# 4_Sensing.net
KiCad netlist of a schematic drawn in Altium Designer
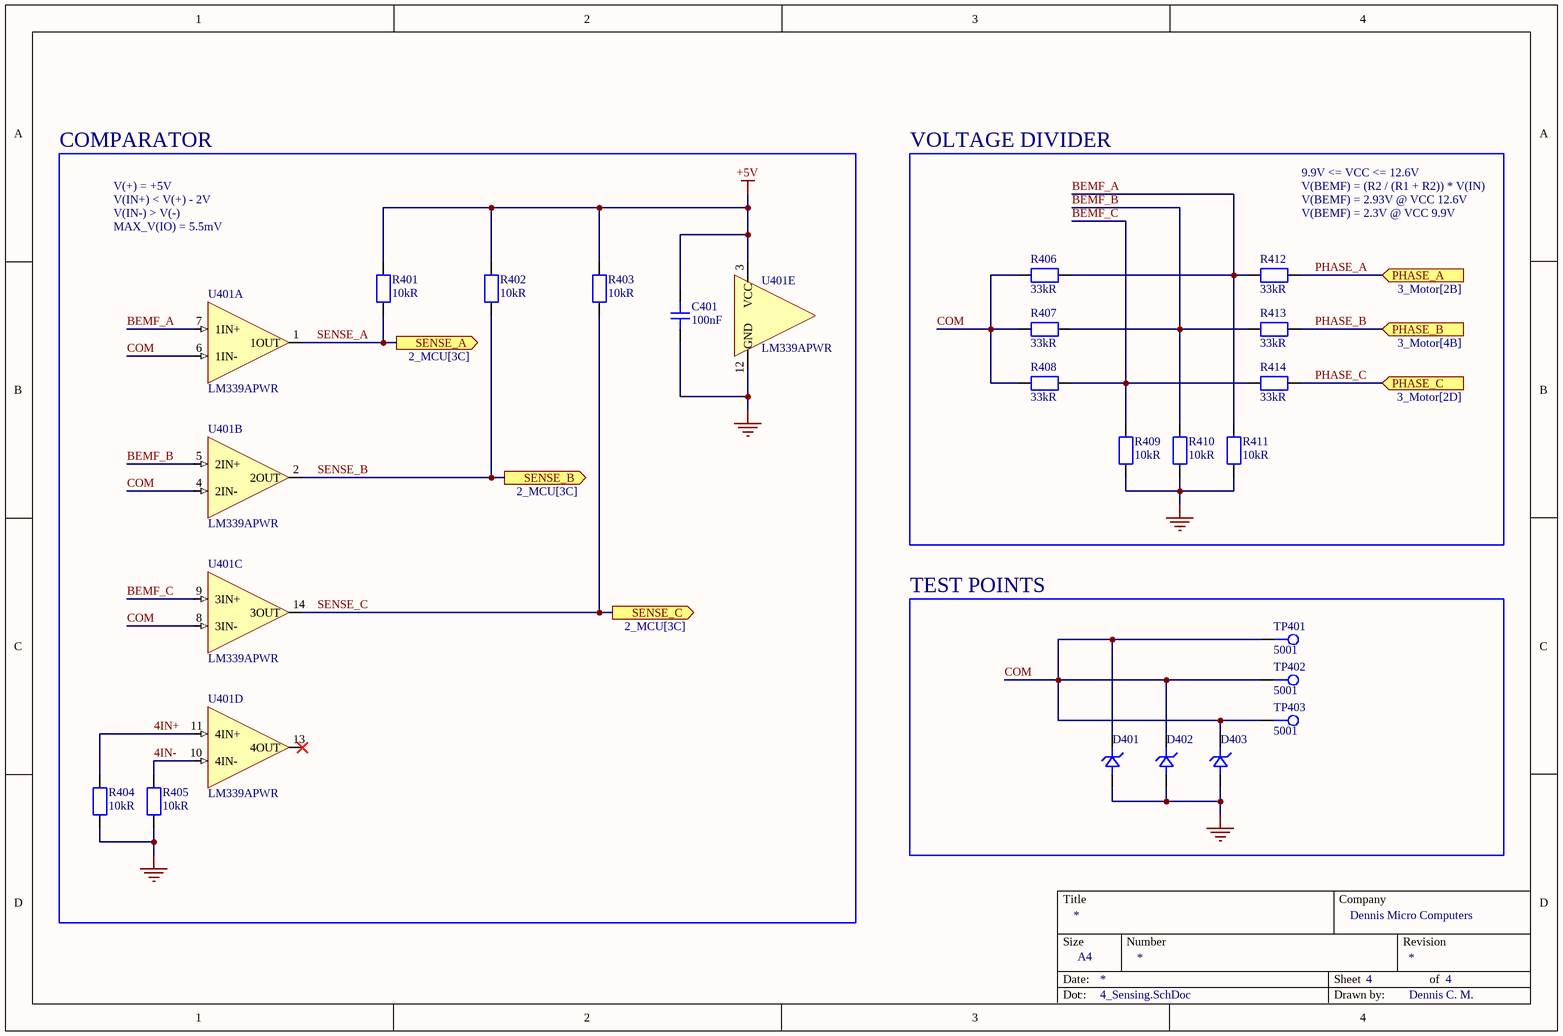
[diagram p0: 4_Sensing.SchDoc]

(export (version "E")
  (design (tool "Eeschema 10.0.6"))
  (components
    (comp (ref "C401")
      (value "100nF")
      (footprint "C_Samsung_CL_0402_A")
      (description "Multilayer Ceramic Capacitor, 0.1 uF, 10 V, ± 10%, X7R, 0402 [1005 Metric]")
      (fields (field (name "TOLERANCE") "10%") (field (name "Comment") "CL05B104KP5NNNC"))
      (libsource (lib "Dennis Micro Computers") (part "C"))
    )
    (comp (ref "D401")
      (value "SMBJ15A-13-F")
      (footprint "D_TVS_Uni_Diodes_DO-214AA_B")
      (description "TVS Diode Single Uni-Dir 15V 600W 2-Pin SMB T/R / TVS DIODE 15VWM 24.4VC SMB")
      (libsource (lib "Dennis Micro Computers") (part "D_TVS_Uni"))
    )
    (comp (ref "D402")
      (value "SMBJ15A-13-F")
      (footprint "D_TVS_Uni_Diodes_DO-214AA_B")
      (description "TVS Diode Single Uni-Dir 15V 600W 2-Pin SMB T/R / TVS DIODE 15VWM 24.4VC SMB")
      (libsource (lib "Dennis Micro Computers") (part "D_TVS_Uni"))
    )
    (comp (ref "D403")
      (value "SMBJ15A-13-F")
      (footprint "D_TVS_Uni_Diodes_DO-214AA_B")
      (description "TVS Diode Single Uni-Dir 15V 600W 2-Pin SMB T/R / TVS DIODE 15VWM 24.4VC SMB")
      (libsource (lib "Dennis Micro Computers") (part "D_TVS_Uni"))
    )
    (comp (ref "R401")
      (value "10kR")
      (footprint "R_Yageo_RCL_0402_A")
      (description "SMD Chip Resistor, 10 kOhm, ± 1%, 62.5 mW, 0402 [1005 Metric], Thick Film, General Purpose")
      (fields (field (name "TOLERANCE") "1%") (field (name "Comment") "RC0402FR-0710KL"))
      (libsource (lib "Dennis Micro Computers") (part "R"))
    )
    (comp (ref "R402")
      (value "10kR")
      (footprint "R_Yageo_RCL_0402_A")
      (description "SMD Chip Resistor, 10 kOhm, ± 1%, 62.5 mW, 0402 [1005 Metric], Thick Film, General Purpose")
      (fields (field (name "TOLERANCE") "1%") (field (name "Comment") "RC0402FR-0710KL"))
      (libsource (lib "Dennis Micro Computers") (part "R"))
    )
    (comp (ref "R403")
      (value "10kR")
      (footprint "R_Yageo_RCL_0402_A")
      (description "SMD Chip Resistor, 10 kOhm, ± 1%, 62.5 mW, 0402 [1005 Metric], Thick Film, General Purpose")
      (fields (field (name "TOLERANCE") "1%") (field (name "Comment") "RC0402FR-0710KL"))
      (libsource (lib "Dennis Micro Computers") (part "R"))
    )
    (comp (ref "R404")
      (value "10kR")
      (footprint "R_Yageo_RCL_0402_A")
      (description "SMD Chip Resistor, 10 kOhm, ± 1%, 62.5 mW, 0402 [1005 Metric], Thick Film, General Purpose")
      (fields (field (name "TOLERANCE") "1%") (field (name "Comment") "RC0402FR-0710KL"))
      (libsource (lib "Dennis Micro Computers") (part "R"))
    )
    (comp (ref "R405")
      (value "10kR")
      (footprint "R_Yageo_RCL_0402_A")
      (description "SMD Chip Resistor, 10 kOhm, ± 1%, 62.5 mW, 0402 [1005 Metric], Thick Film, General Purpose")
      (fields (field (name "TOLERANCE") "1%") (field (name "Comment") "RC0402FR-0710KL"))
      (libsource (lib "Dennis Micro Computers") (part "R"))
    )
    (comp (ref "R406")
      (value "33kR")
      (footprint "R_Yageo_RCL_0402_A")
      (description "SMD Chip Resistor, 33 kOhm, ± 1%, 63 mW, 0402 [1005 Metric], Thick Film, General Purpose")
      (fields (field (name "TOLERANCE") "1%") (field (name "Comment") "RC0402FR-0733KL"))
      (libsource (lib "Dennis Micro Computers") (part "R"))
    )
    (comp (ref "R407")
      (value "33kR")
      (footprint "R_Yageo_RCL_0402_A")
      (description "SMD Chip Resistor, 33 kOhm, ± 1%, 63 mW, 0402 [1005 Metric], Thick Film, General Purpose")
      (fields (field (name "TOLERANCE") "1%") (field (name "Comment") "RC0402FR-0733KL"))
      (libsource (lib "Dennis Micro Computers") (part "R"))
    )
    (comp (ref "R408")
      (value "33kR")
      (footprint "R_Yageo_RCL_0402_A")
      (description "SMD Chip Resistor, 33 kOhm, ± 1%, 63 mW, 0402 [1005 Metric], Thick Film, General Purpose")
      (fields (field (name "TOLERANCE") "1%") (field (name "Comment") "RC0402FR-0733KL"))
      (libsource (lib "Dennis Micro Computers") (part "R"))
    )
    (comp (ref "R409")
      (value "10kR")
      (footprint "R_Yageo_RCL_0402_A")
      (description "SMD Chip Resistor, 10 kOhm, ± 1%, 62.5 mW, 0402 [1005 Metric], Thick Film, General Purpose")
      (fields (field (name "TOLERANCE") "1%") (field (name "Comment") "RC0402FR-0710KL"))
      (libsource (lib "Dennis Micro Computers") (part "R"))
    )
    (comp (ref "R410")
      (value "10kR")
      (footprint "R_Yageo_RCL_0402_A")
      (description "SMD Chip Resistor, 10 kOhm, ± 1%, 62.5 mW, 0402 [1005 Metric], Thick Film, General Purpose")
      (fields (field (name "TOLERANCE") "1%") (field (name "Comment") "RC0402FR-0710KL"))
      (libsource (lib "Dennis Micro Computers") (part "R"))
    )
    (comp (ref "R411")
      (value "10kR")
      (footprint "R_Yageo_RCL_0402_A")
      (description "SMD Chip Resistor, 10 kOhm, ± 1%, 62.5 mW, 0402 [1005 Metric], Thick Film, General Purpose")
      (fields (field (name "TOLERANCE") "1%") (field (name "Comment") "RC0402FR-0710KL"))
      (libsource (lib "Dennis Micro Computers") (part "R"))
    )
    (comp (ref "R412")
      (value "33kR")
      (footprint "R_Yageo_RCL_0402_A")
      (description "SMD Chip Resistor, 33 kOhm, ± 1%, 63 mW, 0402 [1005 Metric], Thick Film, General Purpose")
      (fields (field (name "TOLERANCE") "1%") (field (name "Comment") "RC0402FR-0733KL"))
      (libsource (lib "Dennis Micro Computers") (part "R"))
    )
    (comp (ref "R413")
      (value "33kR")
      (footprint "R_Yageo_RCL_0402_A")
      (description "SMD Chip Resistor, 33 kOhm, ± 1%, 63 mW, 0402 [1005 Metric], Thick Film, General Purpose")
      (fields (field (name "TOLERANCE") "1%") (field (name "Comment") "RC0402FR-0733KL"))
      (libsource (lib "Dennis Micro Computers") (part "R"))
    )
    (comp (ref "R414")
      (value "33kR")
      (footprint "R_Yageo_RCL_0402_A")
      (description "SMD Chip Resistor, 33 kOhm, ± 1%, 63 mW, 0402 [1005 Metric], Thick Film, General Purpose")
      (fields (field (name "TOLERANCE") "1%") (field (name "Comment") "RC0402FR-0733KL"))
      (libsource (lib "Dennis Micro Computers") (part "R"))
    )
    (comp (ref "TP401")
      (value "5001")
      (footprint "TP_Keystone_TH")
      (libsource (lib "Dennis Micro Computers") (part "TP"))
    )
    (comp (ref "TP402")
      (value "5001")
      (footprint "TP_Keystone_TH")
      (libsource (lib "Dennis Micro Computers") (part "TP"))
    )
    (comp (ref "TP403")
      (value "5001")
      (footprint "TP_Keystone_TH")
      (libsource (lib "Dennis Micro Computers") (part "TP"))
    )
    (comp (ref "U401")
      (value "LM339APWR")
      (footprint "U_TI_14-TSSOP-5.00x4.40mm_0.62mm_B")
      (description "Precision quad differential comparator, commercial grade 14-TSSOP 0 to 70")
      (libsource (lib "Dennis Micro Computers") (part "U_LM339APWR"))
    )
  )
  (nets
    (net (code "1") (name "+5V") (class "Default")
      (node (ref "C401") (pin "2") (pinfunction "2_2") (pintype "passive"))
      (node (ref "R401") (pin "2") (pinfunction "2_2") (pintype "passive"))
      (node (ref "R402") (pin "2") (pinfunction "2_2") (pintype "passive"))
      (node (ref "R403") (pin "2") (pinfunction "2_2") (pintype "passive"))
      (node (ref "U401") (pin "3") (pinfunction "VCC_3") (pintype "power_in"))
    )
    (net (code "2") (name "/4IN+") (class "Default")
      (node (ref "R404") (pin "2") (pinfunction "2_2") (pintype "passive"))
      (node (ref "U401") (pin "11") (pinfunction "4IN+_11") (pintype "input"))
    )
    (net (code "3") (name "/4IN-") (class "Default")
      (node (ref "R405") (pin "2") (pinfunction "2_2") (pintype "passive"))
      (node (ref "U401") (pin "10") (pinfunction "4IN-_10") (pintype "input"))
    )
    (net (code "4") (name "/BEMF_A") (class "Default")
      (node (ref "R406") (pin "2") (pinfunction "2_2") (pintype "passive"))
      (node (ref "R411") (pin "2") (pinfunction "2_2") (pintype "passive"))
      (node (ref "R412") (pin "1") (pinfunction "1_1") (pintype "passive"))
      (node (ref "U401") (pin "7") (pinfunction "1IN+_7") (pintype "input"))
    )
    (net (code "5") (name "/BEMF_B") (class "Default")
      (node (ref "R407") (pin "2") (pinfunction "2_2") (pintype "passive"))
      (node (ref "R410") (pin "2") (pinfunction "2_2") (pintype "passive"))
      (node (ref "R413") (pin "1") (pinfunction "1_1") (pintype "passive"))
      (node (ref "U401") (pin "5") (pinfunction "2IN+_5") (pintype "input"))
    )
    (net (code "6") (name "/BEMF_C") (class "Default")
      (node (ref "R408") (pin "2") (pinfunction "2_2") (pintype "passive"))
      (node (ref "R409") (pin "2") (pinfunction "2_2") (pintype "passive"))
      (node (ref "R414") (pin "1") (pinfunction "1_1") (pintype "passive"))
      (node (ref "U401") (pin "9") (pinfunction "3IN+_9") (pintype "input"))
    )
    (net (code "7") (name "/COM") (class "Default")
      (node (ref "D401") (pin "1") (pinfunction "1_1") (pintype "passive"))
      (node (ref "D402") (pin "1") (pinfunction "1_1") (pintype "passive"))
      (node (ref "D403") (pin "1") (pinfunction "1_1") (pintype "passive"))
      (node (ref "R406") (pin "1") (pinfunction "1_1") (pintype "passive"))
      (node (ref "R407") (pin "1") (pinfunction "1_1") (pintype "passive"))
      (node (ref "R408") (pin "1") (pinfunction "1_1") (pintype "passive"))
      (node (ref "TP401") (pin "1") (pinfunction "1_1") (pintype "passive"))
      (node (ref "TP402") (pin "1") (pinfunction "1_1") (pintype "passive"))
      (node (ref "TP403") (pin "1") (pinfunction "1_1") (pintype "passive"))
      (node (ref "U401") (pin "4") (pinfunction "2IN-_4") (pintype "input"))
      (node (ref "U401") (pin "6") (pinfunction "1IN-_6") (pintype "input"))
      (node (ref "U401") (pin "8") (pinfunction "3IN-_8") (pintype "input"))
    )
    (net (code "8") (name "/PHASE_A") (class "Default")
      (node (ref "R412") (pin "2") (pinfunction "2_2") (pintype "passive"))
    )
    (net (code "9") (name "/PHASE_B") (class "Default")
      (node (ref "R413") (pin "2") (pinfunction "2_2") (pintype "passive"))
    )
    (net (code "10") (name "/PHASE_C") (class "Default")
      (node (ref "R414") (pin "2") (pinfunction "2_2") (pintype "passive"))
    )
    (net (code "11") (name "/SENSE_A") (class "Default")
      (node (ref "R401") (pin "1") (pinfunction "1_1") (pintype "passive"))
      (node (ref "U401") (pin "1") (pinfunction "1OUT_1") (pintype "open_collector"))
    )
    (net (code "12") (name "/SENSE_B") (class "Default")
      (node (ref "R402") (pin "1") (pinfunction "1_1") (pintype "passive"))
      (node (ref "U401") (pin "2") (pinfunction "2OUT_2") (pintype "open_collector"))
    )
    (net (code "13") (name "/SENSE_C") (class "Default")
      (node (ref "R403") (pin "1") (pinfunction "1_1") (pintype "passive"))
      (node (ref "U401") (pin "14") (pinfunction "3OUT_14") (pintype "open_collector"))
    )
    (net (code "14") (name "GND") (class "Default")
      (node (ref "C401") (pin "1") (pinfunction "1_1") (pintype "passive"))
      (node (ref "D401") (pin "2") (pinfunction "2_2") (pintype "passive"))
      (node (ref "D402") (pin "2") (pinfunction "2_2") (pintype "passive"))
      (node (ref "D403") (pin "2") (pinfunction "2_2") (pintype "passive"))
      (node (ref "R404") (pin "1") (pinfunction "1_1") (pintype "passive"))
      (node (ref "R405") (pin "1") (pinfunction "1_1") (pintype "passive"))
      (node (ref "R409") (pin "1") (pinfunction "1_1") (pintype "passive"))
      (node (ref "R410") (pin "1") (pinfunction "1_1") (pintype "passive"))
      (node (ref "R411") (pin "1") (pinfunction "1_1") (pintype "passive"))
      (node (ref "U401") (pin "12") (pinfunction "GND_12") (pintype "power_in"))
    )
    (net (code "15") (name "unconnected-(U401D-4OUT-Pad13)") (class "Default")
      (node (ref "U401") (pin "13") (pinfunction "4OUT_13") (pintype "open_collector+no_connect"))
    )
  )
)
